# Arduino_Board.net
KiCad netlist of a schematic drawn in EAGLE
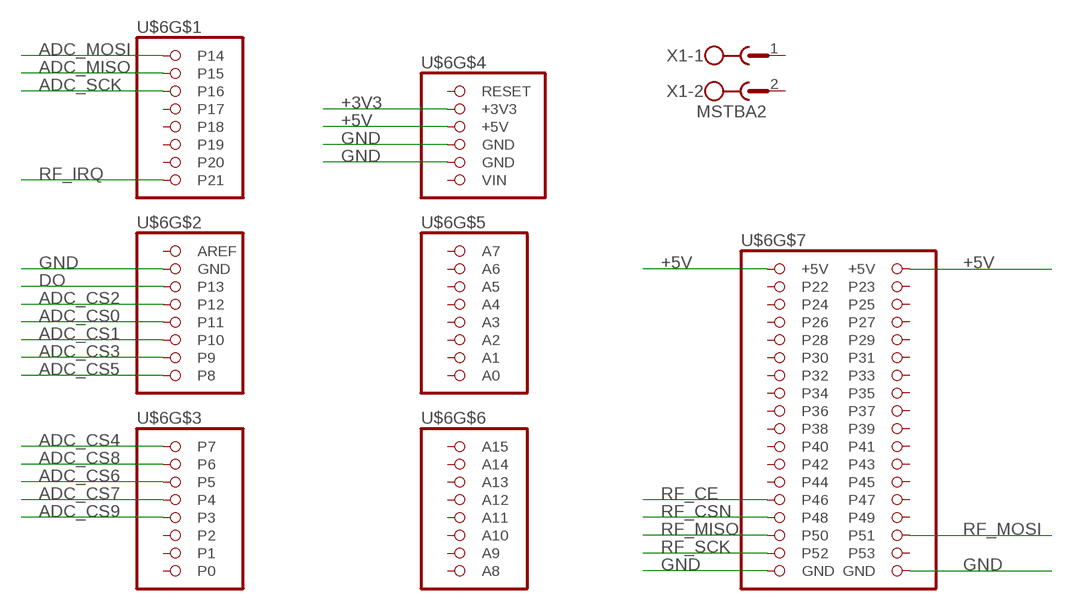
[diagram p0: schematic, sheet 1]
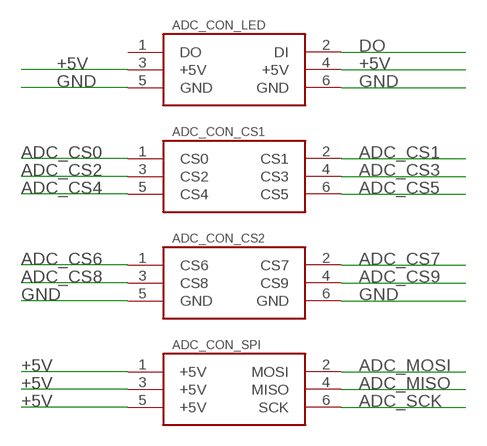
[diagram p1: schematic, sheet 2]
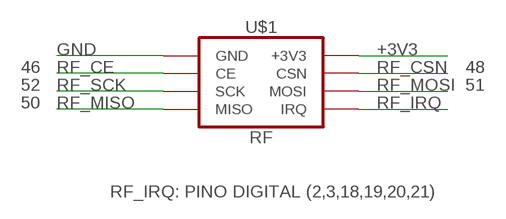
[diagram p2: schematic, sheet 3]

(export (version "E")
  (design (tool "Eeschema 10.0.6"))
  (components
    (comp (ref "U$1") (value "RF") (footprint "eagle-import:RF") (libsource (lib "eagle-import") (part "RF")))
    (comp (ref "U$6")
      (value "ARDUINO_MEGA")
      (footprint "eagle-import:ARDUINO_MEGA")
      (libsource (lib "eagle-import") (part "ARDUINO_MEGA"))
    )
    (comp (ref "X1")
      (value "MSTBA2")
      (footprint "eagle-import:MSTBA2")
      (fields (field (name "MF") "FARNELL") (field (name "MPN") "1757242"))
      (libsource (lib "eagle-import") (part "MSTBA2"))
    )
    (comp (ref "U$2")
      (value "ADC_CON_LED")
      (footprint "eagle-import:T821_2X03")
      (libsource (lib "eagle-import") (part "ADC_CON_LED"))
    )
    (comp (ref "U$3")
      (value "ADC_CON_CS1")
      (footprint "eagle-import:T821_2X03")
      (libsource (lib "eagle-import") (part "ADC_CON_CS1"))
    )
    (comp (ref "U$4")
      (value "ADC_CON_CS2")
      (footprint "eagle-import:T821_2X03")
      (libsource (lib "eagle-import") (part "ADC_CON_CS2"))
    )
    (comp (ref "U$5")
      (value "ADC_CON_SPI")
      (footprint "eagle-import:T821_2X03")
      (libsource (lib "eagle-import") (part "ADC_CON_SPI"))
    )
  )
  (nets
    (net (code "1") (name "+3V3") (class "Default")
      (node (ref "U$1") (pin "2") (pinfunction "+3V3_2") (pintype "passive"))
      (node (ref "U$6") (pin "+3V3") (pinfunction "+3V3_+3V3") (pintype "passive"))
    )
    (net (code "2") (name "+5V") (class "Default")
      (node (ref "U$2") (pin "3") (pinfunction "+5V_3") (pintype "power_in"))
      (node (ref "U$2") (pin "4") (pinfunction "+5V_4") (pintype "power_in"))
      (node (ref "U$5") (pin "1") (pinfunction "+5V_1") (pintype "bidirectional"))
      (node (ref "U$5") (pin "3") (pinfunction "+5V_3") (pintype "bidirectional"))
      (node (ref "U$5") (pin "5") (pinfunction "+5V_5") (pintype "bidirectional"))
      (node (ref "U$6") (pin "+5V@1") (pinfunction "+5V_+5V@1") (pintype "passive"))
      (node (ref "U$6") (pin "+5V@2") (pinfunction "+5V_+5V@2") (pintype "passive"))
      (node (ref "U$6") (pin "+5V@3") (pinfunction "+5V_+5V@3") (pintype "passive"))
    )
    (net (code "3") (name "ADC_CS0") (class "Default")
      (node (ref "U$3") (pin "1") (pinfunction "CS0_1") (pintype "bidirectional"))
      (node (ref "U$6") (pin "P11") (pinfunction "P11_P11") (pintype "passive"))
    )
    (net (code "4") (name "ADC_CS1") (class "Default")
      (node (ref "U$3") (pin "2") (pinfunction "CS1_2") (pintype "bidirectional"))
      (node (ref "U$6") (pin "P10") (pinfunction "P10_P10") (pintype "passive"))
    )
    (net (code "5") (name "ADC_CS2") (class "Default")
      (node (ref "U$3") (pin "3") (pinfunction "CS2_3") (pintype "bidirectional"))
      (node (ref "U$6") (pin "P12") (pinfunction "P12_P12") (pintype "passive"))
    )
    (net (code "6") (name "ADC_CS3") (class "Default")
      (node (ref "U$3") (pin "4") (pinfunction "CS3_4") (pintype "bidirectional"))
      (node (ref "U$6") (pin "P9") (pinfunction "P9_P9") (pintype "passive"))
    )
    (net (code "7") (name "ADC_CS4") (class "Default")
      (node (ref "U$3") (pin "5") (pinfunction "CS4_5") (pintype "bidirectional"))
      (node (ref "U$6") (pin "P7") (pinfunction "P7_P7") (pintype "passive"))
    )
    (net (code "8") (name "ADC_CS5") (class "Default")
      (node (ref "U$3") (pin "6") (pinfunction "CS5_6") (pintype "bidirectional"))
      (node (ref "U$6") (pin "P8") (pinfunction "P8_P8") (pintype "passive"))
    )
    (net (code "9") (name "ADC_CS6") (class "Default")
      (node (ref "U$4") (pin "1") (pinfunction "CS6_1") (pintype "bidirectional"))
      (node (ref "U$6") (pin "P5") (pinfunction "P5_P5") (pintype "passive"))
    )
    (net (code "10") (name "ADC_CS7") (class "Default")
      (node (ref "U$4") (pin "2") (pinfunction "CS7_2") (pintype "bidirectional"))
      (node (ref "U$6") (pin "P4") (pinfunction "P4_P4") (pintype "passive"))
    )
    (net (code "11") (name "ADC_CS8") (class "Default")
      (node (ref "U$4") (pin "3") (pinfunction "CS8_3") (pintype "bidirectional"))
      (node (ref "U$6") (pin "P6") (pinfunction "P6_P6") (pintype "passive"))
    )
    (net (code "12") (name "ADC_CS9") (class "Default")
      (node (ref "U$4") (pin "4") (pinfunction "CS9_4") (pintype "bidirectional"))
      (node (ref "U$6") (pin "P3") (pinfunction "P3_P3") (pintype "passive"))
    )
    (net (code "13") (name "ADC_MISO") (class "Default")
      (node (ref "U$5") (pin "4") (pinfunction "MISO_4") (pintype "bidirectional"))
      (node (ref "U$6") (pin "P15") (pinfunction "P15_P15") (pintype "passive"))
    )
    (net (code "14") (name "ADC_MOSI") (class "Default")
      (node (ref "U$5") (pin "2") (pinfunction "MOSI_2") (pintype "bidirectional"))
      (node (ref "U$6") (pin "P14") (pinfunction "P14_P14") (pintype "passive"))
    )
    (net (code "15") (name "ADC_SCK") (class "Default")
      (node (ref "U$5") (pin "6") (pinfunction "SCK_6") (pintype "bidirectional"))
      (node (ref "U$6") (pin "P16") (pinfunction "P16_P16") (pintype "passive"))
    )
    (net (code "16") (name "DO") (class "Default")
      (node (ref "U$2") (pin "2") (pinfunction "DI_2") (pintype "bidirectional"))
      (node (ref "U$6") (pin "P13") (pinfunction "P13_P13") (pintype "passive"))
    )
    (net (code "17") (name "GND") (class "Default")
      (node (ref "U$1") (pin "1") (pinfunction "GND_1") (pintype "passive"))
      (node (ref "U$2") (pin "5") (pinfunction "GND_5") (pintype "power_in"))
      (node (ref "U$2") (pin "6") (pinfunction "GND_6") (pintype "power_in"))
      (node (ref "U$4") (pin "5") (pinfunction "GND_5") (pintype "power_in"))
      (node (ref "U$4") (pin "6") (pinfunction "GND_6") (pintype "power_in"))
      (node (ref "U$6") (pin "GND@1") (pinfunction "GND_GND@1") (pintype "passive"))
      (node (ref "U$6") (pin "GND@2") (pinfunction "GND_GND@2") (pintype "passive"))
      (node (ref "U$6") (pin "GND@3") (pinfunction "GND_GND@3") (pintype "passive"))
      (node (ref "U$6") (pin "GND@4") (pinfunction "GND_GND@4") (pintype "passive"))
      (node (ref "U$6") (pin "GND@5") (pinfunction "GND_GND@5") (pintype "passive"))
    )
    (net (code "18") (name "RF_CE") (class "Default")
      (node (ref "U$1") (pin "3") (pinfunction "CE_3") (pintype "passive"))
      (node (ref "U$6") (pin "P46") (pinfunction "P46_P46") (pintype "passive"))
    )
    (net (code "19") (name "RF_CSN") (class "Default")
      (node (ref "U$1") (pin "4") (pinfunction "CSN_4") (pintype "passive"))
      (node (ref "U$6") (pin "P48") (pinfunction "P48_P48") (pintype "passive"))
    )
    (net (code "20") (name "RF_IRQ") (class "Default")
      (node (ref "U$1") (pin "8") (pinfunction "IRQ_8") (pintype "passive"))
      (node (ref "U$6") (pin "P21") (pinfunction "P21_P21") (pintype "passive"))
    )
    (net (code "21") (name "RF_MISO") (class "Default")
      (node (ref "U$1") (pin "7") (pinfunction "MISO_7") (pintype "passive"))
      (node (ref "U$6") (pin "P50") (pinfunction "P50_P50") (pintype "passive"))
    )
    (net (code "22") (name "RF_MOSI") (class "Default")
      (node (ref "U$1") (pin "6") (pinfunction "MOSI_6") (pintype "passive"))
      (node (ref "U$6") (pin "P51") (pinfunction "P51_P51") (pintype "passive"))
    )
    (net (code "23") (name "RF_SCK") (class "Default")
      (node (ref "U$1") (pin "5") (pinfunction "SCK_5") (pintype "passive"))
      (node (ref "U$6") (pin "P52") (pinfunction "P52_P52") (pintype "passive"))
    )
    (net (code "24") (name "unconnected-(U$2-DO-Pad1)") (class "Default")
      (node (ref "U$2") (pin "1") (pinfunction "DO_1") (pintype "bidirectional"))
    )
    (net (code "25") (name "unconnected-(U$6-PadA0)") (class "Default")
      (node (ref "U$6") (pin "A0") (pinfunction "A0_A0") (pintype "passive"))
    )
    (net (code "26") (name "unconnected-(U$6-PadA1)") (class "Default")
      (node (ref "U$6") (pin "A1") (pinfunction "A1_A1") (pintype "passive"))
    )
    (net (code "27") (name "unconnected-(U$6-PadA2)") (class "Default")
      (node (ref "U$6") (pin "A2") (pinfunction "A2_A2") (pintype "passive"))
    )
    (net (code "28") (name "unconnected-(U$6-PadA3)") (class "Default")
      (node (ref "U$6") (pin "A3") (pinfunction "A3_A3") (pintype "passive"))
    )
    (net (code "29") (name "unconnected-(U$6-PadA4)") (class "Default")
      (node (ref "U$6") (pin "A4") (pinfunction "A4_A4") (pintype "passive"))
    )
    (net (code "30") (name "unconnected-(U$6-PadA5)") (class "Default")
      (node (ref "U$6") (pin "A5") (pinfunction "A5_A5") (pintype "passive"))
    )
    (net (code "31") (name "unconnected-(U$6-PadA6)") (class "Default")
      (node (ref "U$6") (pin "A6") (pinfunction "A6_A6") (pintype "passive"))
    )
    (net (code "32") (name "unconnected-(U$6-PadA7)") (class "Default")
      (node (ref "U$6") (pin "A7") (pinfunction "A7_A7") (pintype "passive"))
    )
    (net (code "33") (name "unconnected-(U$6-PadA8)") (class "Default")
      (node (ref "U$6") (pin "A8") (pinfunction "A8_A8") (pintype "passive"))
    )
    (net (code "34") (name "unconnected-(U$6-PadA9)") (class "Default")
      (node (ref "U$6") (pin "A9") (pinfunction "A9_A9") (pintype "passive"))
    )
    (net (code "35") (name "unconnected-(U$6-PadA10)") (class "Default")
      (node (ref "U$6") (pin "A10") (pinfunction "A10_A10") (pintype "passive"))
    )
    (net (code "36") (name "unconnected-(U$6-PadA11)") (class "Default")
      (node (ref "U$6") (pin "A11") (pinfunction "A11_A11") (pintype "passive"))
    )
    (net (code "37") (name "unconnected-(U$6-PadA12)") (class "Default")
      (node (ref "U$6") (pin "A12") (pinfunction "A12_A12") (pintype "passive"))
    )
    (net (code "38") (name "unconnected-(U$6-PadA13)") (class "Default")
      (node (ref "U$6") (pin "A13") (pinfunction "A13_A13") (pintype "passive"))
    )
    (net (code "39") (name "unconnected-(U$6-PadA14)") (class "Default")
      (node (ref "U$6") (pin "A14") (pinfunction "A14_A14") (pintype "passive"))
    )
    (net (code "40") (name "unconnected-(U$6-PadA15)") (class "Default")
      (node (ref "U$6") (pin "A15") (pinfunction "A15_A15") (pintype "passive"))
    )
    (net (code "41") (name "unconnected-(U$6-PadAREF)") (class "Default")
      (node (ref "U$6") (pin "AREF") (pinfunction "AREF_AREF") (pintype "passive"))
    )
    (net (code "42") (name "unconnected-(U$6-PadP0)") (class "Default")
      (node (ref "U$6") (pin "P0") (pinfunction "P0_P0") (pintype "passive"))
    )
    (net (code "43") (name "unconnected-(U$6-PadP1)") (class "Default")
      (node (ref "U$6") (pin "P1") (pinfunction "P1_P1") (pintype "passive"))
    )
    (net (code "44") (name "unconnected-(U$6-PadP2)") (class "Default")
      (node (ref "U$6") (pin "P2") (pinfunction "P2_P2") (pintype "passive"))
    )
    (net (code "45") (name "unconnected-(U$6-PadP17)") (class "Default")
      (node (ref "U$6") (pin "P17") (pinfunction "P17_P17") (pintype "passive"))
    )
    (net (code "46") (name "unconnected-(U$6-PadP18)") (class "Default")
      (node (ref "U$6") (pin "P18") (pinfunction "P18_P18") (pintype "passive"))
    )
    (net (code "47") (name "unconnected-(U$6-PadP19)") (class "Default")
      (node (ref "U$6") (pin "P19") (pinfunction "P19_P19") (pintype "passive"))
    )
    (net (code "48") (name "unconnected-(U$6-PadP20)") (class "Default")
      (node (ref "U$6") (pin "P20") (pinfunction "P20_P20") (pintype "passive"))
    )
    (net (code "49") (name "unconnected-(U$6-PadP22)") (class "Default")
      (node (ref "U$6") (pin "P22") (pinfunction "P22_P22") (pintype "passive"))
    )
    (net (code "50") (name "unconnected-(U$6-PadP23)") (class "Default")
      (node (ref "U$6") (pin "P23") (pinfunction "P23_P23") (pintype "passive"))
    )
    (net (code "51") (name "unconnected-(U$6-PadP24)") (class "Default")
      (node (ref "U$6") (pin "P24") (pinfunction "P24_P24") (pintype "passive"))
    )
    (net (code "52") (name "unconnected-(U$6-PadP25)") (class "Default")
      (node (ref "U$6") (pin "P25") (pinfunction "P25_P25") (pintype "passive"))
    )
    (net (code "53") (name "unconnected-(U$6-PadP26)") (class "Default")
      (node (ref "U$6") (pin "P26") (pinfunction "P26_P26") (pintype "passive"))
    )
    (net (code "54") (name "unconnected-(U$6-PadP27)") (class "Default")
      (node (ref "U$6") (pin "P27") (pinfunction "P27_P27") (pintype "passive"))
    )
    (net (code "55") (name "unconnected-(U$6-PadP28)") (class "Default")
      (node (ref "U$6") (pin "P28") (pinfunction "P28_P28") (pintype "passive"))
    )
    (net (code "56") (name "unconnected-(U$6-PadP29)") (class "Default")
      (node (ref "U$6") (pin "P29") (pinfunction "P29_P29") (pintype "passive"))
    )
    (net (code "57") (name "unconnected-(U$6-PadP30)") (class "Default")
      (node (ref "U$6") (pin "P30") (pinfunction "P30_P30") (pintype "passive"))
    )
    (net (code "58") (name "unconnected-(U$6-PadP31)") (class "Default")
      (node (ref "U$6") (pin "P31") (pinfunction "P31_P31") (pintype "passive"))
    )
    (net (code "59") (name "unconnected-(U$6-PadP32)") (class "Default")
      (node (ref "U$6") (pin "P32") (pinfunction "P32_P32") (pintype "passive"))
    )
    (net (code "60") (name "unconnected-(U$6-PadP33)") (class "Default")
      (node (ref "U$6") (pin "P33") (pinfunction "P33_P33") (pintype "passive"))
    )
    (net (code "61") (name "unconnected-(U$6-PadP34)") (class "Default")
      (node (ref "U$6") (pin "P34") (pinfunction "P34_P34") (pintype "passive"))
    )
    (net (code "62") (name "unconnected-(U$6-PadP35)") (class "Default")
      (node (ref "U$6") (pin "P35") (pinfunction "P35_P35") (pintype "passive"))
    )
    (net (code "63") (name "unconnected-(U$6-PadP36)") (class "Default")
      (node (ref "U$6") (pin "P36") (pinfunction "P36_P36") (pintype "passive"))
    )
    (net (code "64") (name "unconnected-(U$6-PadP37)") (class "Default")
      (node (ref "U$6") (pin "P37") (pinfunction "P37_P37") (pintype "passive"))
    )
    (net (code "65") (name "unconnected-(U$6-PadP38)") (class "Default")
      (node (ref "U$6") (pin "P38") (pinfunction "P38_P38") (pintype "passive"))
    )
    (net (code "66") (name "unconnected-(U$6-PadP39)") (class "Default")
      (node (ref "U$6") (pin "P39") (pinfunction "P39_P39") (pintype "passive"))
    )
    (net (code "67") (name "unconnected-(U$6-PadP40)") (class "Default")
      (node (ref "U$6") (pin "P40") (pinfunction "P40_P40") (pintype "passive"))
    )
    (net (code "68") (name "unconnected-(U$6-PadP41)") (class "Default")
      (node (ref "U$6") (pin "P41") (pinfunction "P41_P41") (pintype "passive"))
    )
    (net (code "69") (name "unconnected-(U$6-PadP42)") (class "Default")
      (node (ref "U$6") (pin "P42") (pinfunction "P42_P42") (pintype "passive"))
    )
    (net (code "70") (name "unconnected-(U$6-PadP43)") (class "Default")
      (node (ref "U$6") (pin "P43") (pinfunction "P43_P43") (pintype "passive"))
    )
    (net (code "71") (name "unconnected-(U$6-PadP44)") (class "Default")
      (node (ref "U$6") (pin "P44") (pinfunction "P44_P44") (pintype "passive"))
    )
    (net (code "72") (name "unconnected-(U$6-PadP45)") (class "Default")
      (node (ref "U$6") (pin "P45") (pinfunction "P45_P45") (pintype "passive"))
    )
    (net (code "73") (name "unconnected-(U$6-PadP47)") (class "Default")
      (node (ref "U$6") (pin "P47") (pinfunction "P47_P47") (pintype "passive"))
    )
    (net (code "74") (name "unconnected-(U$6-PadP49)") (class "Default")
      (node (ref "U$6") (pin "P49") (pinfunction "P49_P49") (pintype "passive"))
    )
    (net (code "75") (name "unconnected-(U$6-PadP53)") (class "Default")
      (node (ref "U$6") (pin "P53") (pinfunction "P53_P53") (pintype "passive"))
    )
    (net (code "76") (name "unconnected-(U$6-PadRESET)") (class "Default")
      (node (ref "U$6") (pin "RESET") (pinfunction "RESET_RESET") (pintype "passive"))
    )
    (net (code "77") (name "unconnected-(U$6-PadVIN)") (class "Default")
      (node (ref "U$6") (pin "VIN") (pinfunction "VIN_VIN") (pintype "passive"))
    )
    (net (code "78") (name "unconnected-(X1-Pad1)") (class "Default")
      (node (ref "X1") (pin "1") (pinfunction "1_1") (pintype "passive"))
    )
    (net (code "79") (name "unconnected-(X1B-1-Pad2)") (class "Default")
      (node (ref "X1") (pin "2") (pinfunction "1_2") (pintype "passive"))
    )
  )
)
